# 5_-Motor_Driver_Schematic.net
KiCad netlist of a schematic drawn in Altium Designer
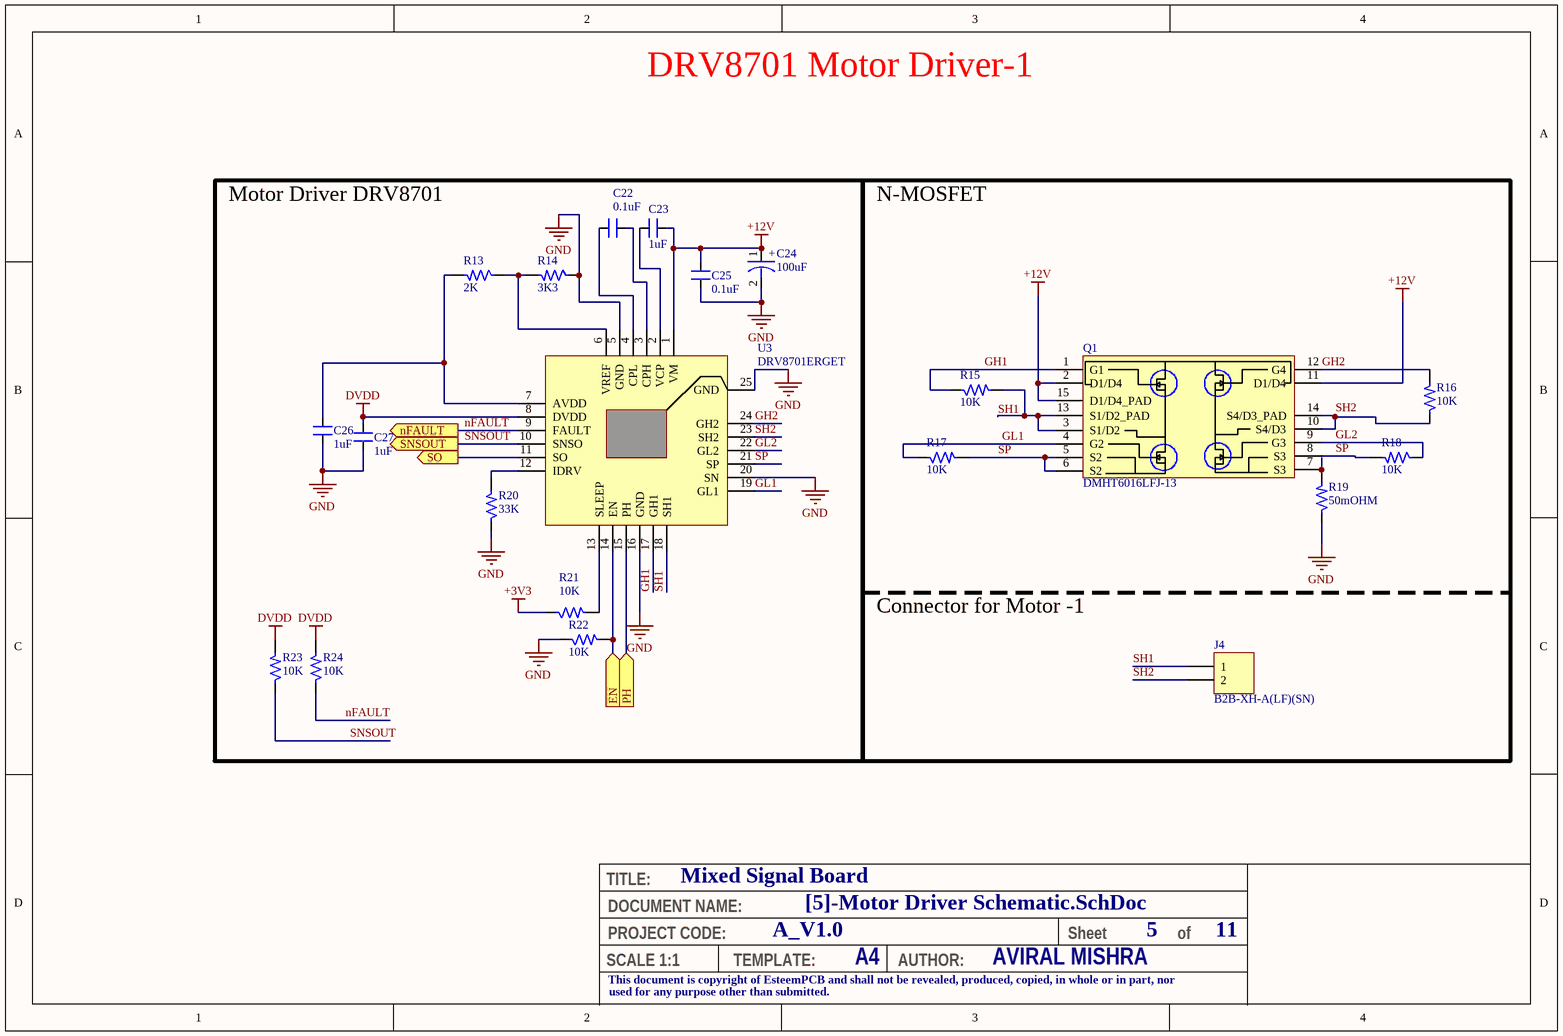
[diagram p0: [5]-Motor Driver Schematic.SchDoc]

(export (version "E")
  (design (tool "Eeschema 10.0.6"))
  (components
    (comp (ref "C22")
      (value "0.1uF")
      (footprint "CAP_0805")
      (description "0.1µF ±10% 50V Ceramic Capacitor X7R 0805 (2012 Metric)")
      (fields
        (field (name "MANUFACTURER") "Samsung")
        (field (name "MANUFACTURER PART NUMBER") "CL21B104KBCNNNC")
      )
      (libsource (lib "ESTEEMPCBLIB") (part "CAP_0.1uF-50V-10%-0805"))
    )
    (comp (ref "C23")
      (value "1uF")
      (footprint "CAP_0805")
      (description "1µF ±5% 50V Ceramic Capacitor X7R 0805 (2012 Metric)")
      (fields
        (field (name "MANUFACTURER") "Samsung")
        (field (name "MANUFACTURER PART NUMBER") "CC0805JKX7R9BB105")
      )
      (libsource (lib "ESTEEMPCBLIB") (part "CAP_1uF-50V-5%-0805"))
    )
    (comp (ref "C24")
      (value "100uF")
      (footprint "ACAP_P236_D305_H303_RAD")
      (description "100µF 25V Aluminum Electrolytic Capacitors Radial, Can - SMD 1000 Hrs @ 105°C")
      (fields
        (field (name "MANUFACTURER") "Nichicon")
        (field (name "MANUFACTURER PART NUMBER") "UWT1E101MCL1GS")
      )
      (libsource (lib "ESTEEMPCBLIB") (part "CAP-P_100uF-25V-20%-RAD"))
    )
    (comp (ref "C25")
      (value "0.1uF")
      (footprint "CAP_0805")
      (description "0.1µF ±10% 50V Ceramic Capacitor X7R 0805 (2012 Metric)")
      (fields
        (field (name "MANUFACTURER") "Samsung")
        (field (name "MANUFACTURER PART NUMBER") "CL21B104KBCNNNC")
      )
      (libsource (lib "ESTEEMPCBLIB") (part "CAP_0.1uF-50V-10%-0805"))
    )
    (comp (ref "C26")
      (value "1uF")
      (footprint "CAP_0805")
      (description "1µF ±5% 50V Ceramic Capacitor X7R 0805 (2012 Metric)")
      (fields
        (field (name "MANUFACTURER") "Samsung")
        (field (name "MANUFACTURER PART NUMBER") "CC0805JKX7R9BB105")
      )
      (libsource (lib "ESTEEMPCBLIB") (part "CAP_1uF-50V-5%-0805"))
    )
    (comp (ref "C27")
      (value "1uF")
      (footprint "CAP_0805")
      (description "1µF ±5% 50V Ceramic Capacitor X7R 0805 (2012 Metric)")
      (fields
        (field (name "MANUFACTURER") "Samsung")
        (field (name "MANUFACTURER PART NUMBER") "CC0805JKX7R9BB105")
      )
      (libsource (lib "ESTEEMPCBLIB") (part "CAP_1uF-50V-5%-0805"))
    )
    (comp (ref "J4")
      (value "B2B-XH-A(LF)(SN)")
      (footprint "CON2_100_B2B-XH-A_TH_ST")
      (description "2 Pins, 1 Row 2.54mm Pitch, Straight Connector, male")
      (fields (field (name "MANUFACTURER") "JST") (field (name "MATING PART NUMBER") "XHP-2"))
      (libsource (lib "ESTEEMPCBLIB") (part "CON-PLG_2X1-100-ST-TH"))
    )
    (comp (ref "Q1")
      (value "DMHT6016LFJ-13")
      (footprint "DFN5045-12_33_212_27X15_SMD_1")
      (description "Mosfet Array 4 N-Channel 14.8A (Ta) Surface Mount V-DFN5045-12")
      (fields (field (name "MANUFACTURER") "ON Semiconductor"))
      (libsource (lib "ESTEEMPCBLIB") (part "MOSFET-N_60V-14.8A-V-DFN5045-12"))
    )
    (comp (ref "R13")
      (value "2K")
      (footprint "RES_0603")
      (fields
        (field (name "MANUFACTURER") "Stackpole Electronics")
        (field (name "MANUFACTURER PART NUMBER") "RNCP0603FTD2K00")
      )
      (libsource (lib "ESTEEMPCBLIB") (part "RES_2K-0.125W-1%-0603"))
    )
    (comp (ref "R14")
      (value "3K3")
      (footprint "RES_0603")
      (description "3.3 kOhms ±1% 0.1W, 1/10W Chip Resistor 0603 (1608 Metric) Automotive AEC-Q200 Thick Film")
      (fields (field (name "MANUFACTURER") "Wilson") (field (name "MANUFACTURER PART NUMBER") "WR06X3301FTL"))
      (libsource (lib "ESTEEMPCBLIB") (part "RES_3.3K-0.1W-1%-0603"))
    )
    (comp (ref "R15")
      (value "10K")
      (footprint "RES_0603")
      (description "10 kOhms ±1% 0.1W, 1/10W Chip Resistor 0603 (1608 Metric) Automotive AEC-Q200 Thick Film")
      (fields (field (name "MANUFACTURER") "Walsin") (field (name "MANUFACTURER PART NUMBER") "WR06X1002FTL"))
      (libsource (lib "ESTEEMPCBLIB") (part "RES_10K-0.1W-1%-0603"))
    )
    (comp (ref "R16")
      (value "10K")
      (footprint "RES_0603")
      (description "10 kOhms ±1% 0.1W, 1/10W Chip Resistor 0603 (1608 Metric) Automotive AEC-Q200 Thick Film")
      (fields (field (name "MANUFACTURER") "Walsin") (field (name "MANUFACTURER PART NUMBER") "WR06X1002FTL"))
      (libsource (lib "ESTEEMPCBLIB") (part "RES_10K-0.1W-1%-0603"))
    )
    (comp (ref "R17")
      (value "10K")
      (footprint "RES_0603")
      (description "10 kOhms ±1% 0.1W, 1/10W Chip Resistor 0603 (1608 Metric) Automotive AEC-Q200 Thick Film")
      (fields (field (name "MANUFACTURER") "Walsin") (field (name "MANUFACTURER PART NUMBER") "WR06X1002FTL"))
      (libsource (lib "ESTEEMPCBLIB") (part "RES_10K-0.1W-1%-0603"))
    )
    (comp (ref "R18")
      (value "10K")
      (footprint "RES_0603")
      (description "10 kOhms ±1% 0.1W, 1/10W Chip Resistor 0603 (1608 Metric) Automotive AEC-Q200 Thick Film")
      (fields (field (name "MANUFACTURER") "Walsin") (field (name "MANUFACTURER PART NUMBER") "WR06X1002FTL"))
      (libsource (lib "ESTEEMPCBLIB") (part "RES_10K-0.1W-1%-0603"))
    )
    (comp (ref "R19")
      (value "50mOHM")
      (footprint "RES_2512")
      (fields
        (field (name "MANUFACTURER") "Yageo")
        (field (name "MANUFACTURER PART NUMBER") "PA2512FKF7W0R05E")
      )
      (libsource (lib "ESTEEMPCBLIB") (part "RES_50mOhm-2W-1%-2512"))
    )
    (comp (ref "R20")
      (value "33K")
      (footprint "RES_0805")
      (fields
        (field (name "MANUFACTURER") "Vishay BCcomponents")
        (field (name "MANUFACTURER PART NUMBER") "CRG0805F33K")
      )
      (libsource (lib "ESTEEMPCBLIB") (part "RES_33K-0.125W-1%-0805"))
    )
    (comp (ref "R21")
      (value "10K")
      (footprint "RES_0603")
      (description "10 kOhms ±1% 0.1W, 1/10W Chip Resistor 0603 (1608 Metric) Automotive AEC-Q200 Thick Film")
      (fields (field (name "MANUFACTURER") "Walsin") (field (name "MANUFACTURER PART NUMBER") "WR06X1002FTL"))
      (libsource (lib "ESTEEMPCBLIB") (part "RES_10K-0.1W-1%-0603"))
    )
    (comp (ref "R22")
      (value "10K")
      (footprint "RES_0603")
      (description "10 kOhms ±1% 0.1W, 1/10W Chip Resistor 0603 (1608 Metric) Automotive AEC-Q200 Thick Film")
      (fields (field (name "MANUFACTURER") "Walsin") (field (name "MANUFACTURER PART NUMBER") "WR06X1002FTL"))
      (libsource (lib "ESTEEMPCBLIB") (part "RES_10K-0.1W-1%-0603"))
    )
    (comp (ref "R23")
      (value "10K")
      (footprint "RES_0603")
      (description "10 kOhms ±1% 0.1W, 1/10W Chip Resistor 0603 (1608 Metric) Automotive AEC-Q200 Thick Film")
      (fields (field (name "MANUFACTURER") "Walsin") (field (name "MANUFACTURER PART NUMBER") "WR06X1002FTL"))
      (libsource (lib "ESTEEMPCBLIB") (part "RES_10K-0.1W-1%-0603"))
    )
    (comp (ref "R24")
      (value "10K")
      (footprint "RES_0603")
      (description "10 kOhms ±1% 0.1W, 1/10W Chip Resistor 0603 (1608 Metric) Automotive AEC-Q200 Thick Film")
      (fields (field (name "MANUFACTURER") "Walsin") (field (name "MANUFACTURER PART NUMBER") "WR06X1002FTL"))
      (libsource (lib "ESTEEMPCBLIB") (part "RES_10K-0.1W-1%-0603"))
    )
    (comp (ref "U3")
      (value "DRV8701ERGET")
      (footprint "VFQFN24_19.6_196_12X32_SMD_1")
      (description "Motor Driver Power MOSFET Parallel 24-VQFN (4x4)")
      (fields (field (name "MANUFACTURER") "Texas Instruments"))
      (libsource (lib "ESTEEMPCBLIB") (part "IC_DRV8701ERGET"))
    )
  )
  (nets
    (net (code "1") (name "+3V3") (class "Default")
      (node (ref "R21") (pin "1") (pinfunction "1_1") (pintype "passive"))
    )
    (net (code "2") (name "+12V") (class "Default")
      (node (ref "C23") (pin "2") (pinfunction "2_2") (pintype "passive"))
      (node (ref "C24") (pin "1") (pinfunction "1_1") (pintype "passive"))
      (node (ref "C25") (pin "2") (pinfunction "2_2") (pintype "passive"))
      (node (ref "Q1") (pin "11") (pinfunction "D1/D4_11") (pintype "passive"))
      (node (ref "Q1") (pin "15") (pinfunction "D1/D4_PAD_15") (pintype "passive"))
      (node (ref "Q1") (pin "2") (pinfunction "D1/D4_2") (pintype "passive"))
      (node (ref "U3") (pin "1") (pinfunction "VM_1") (pintype "passive"))
    )
    (net (code "3") (name "/EN") (class "Default")
      (node (ref "R22") (pin "2") (pinfunction "2_2") (pintype "passive"))
      (node (ref "U3") (pin "14") (pinfunction "EN_14") (pintype "passive"))
    )
    (net (code "4") (name "/GH1") (class "Default")
      (node (ref "Q1") (pin "1") (pinfunction "G1_1") (pintype "passive"))
      (node (ref "R15") (pin "1") (pinfunction "1_1") (pintype "passive"))
      (node (ref "U3") (pin "17") (pinfunction "GH1_17") (pintype "passive"))
    )
    (net (code "5") (name "/GH2") (class "Default")
      (node (ref "Q1") (pin "12") (pinfunction "G4_12") (pintype "passive"))
      (node (ref "R16") (pin "2") (pinfunction "2_2") (pintype "passive"))
      (node (ref "U3") (pin "24") (pinfunction "GH2_24") (pintype "passive"))
    )
    (net (code "6") (name "/GL1") (class "Default")
      (node (ref "Q1") (pin "4") (pinfunction "G2_4") (pintype "passive"))
      (node (ref "R17") (pin "1") (pinfunction "1_1") (pintype "passive"))
      (node (ref "U3") (pin "19") (pinfunction "GL1_19") (pintype "passive"))
    )
    (net (code "7") (name "/GL2") (class "Default")
      (node (ref "Q1") (pin "9") (pinfunction "G3_9") (pintype "passive"))
      (node (ref "R18") (pin "1") (pinfunction "1_1") (pintype "passive"))
      (node (ref "U3") (pin "22") (pinfunction "GL2_22") (pintype "passive"))
    )
    (net (code "8") (name "/PH") (class "Default")
      (node (ref "U3") (pin "15") (pinfunction "PH_15") (pintype "passive"))
    )
    (net (code "9") (name "/SH1") (class "Default")
      (node (ref "J4") (pin "1") (pinfunction "1_1") (pintype "passive"))
      (node (ref "Q1") (pin "13") (pinfunction "S1/D2_PAD_13") (pintype "passive"))
      (node (ref "Q1") (pin "3") (pinfunction "S1/D2_3") (pintype "passive"))
      (node (ref "R15") (pin "2") (pinfunction "2_2") (pintype "passive"))
      (node (ref "U3") (pin "18") (pinfunction "SH1_18") (pintype "passive"))
    )
    (net (code "10") (name "/SH2") (class "Default")
      (node (ref "J4") (pin "2") (pinfunction "2_2") (pintype "passive"))
      (node (ref "Q1") (pin "10") (pinfunction "S4/D3_10") (pintype "passive"))
      (node (ref "Q1") (pin "14") (pinfunction "S4/D3_PAD_14") (pintype "passive"))
      (node (ref "R16") (pin "1") (pinfunction "1_1") (pintype "passive"))
      (node (ref "U3") (pin "23") (pinfunction "SH2_23") (pintype "passive"))
    )
    (net (code "11") (name "/SNSOUT") (class "Default")
      (node (ref "R23") (pin "1") (pinfunction "1_1") (pintype "passive"))
      (node (ref "U3") (pin "10") (pinfunction "SNSO_10") (pintype "passive"))
    )
    (net (code "12") (name "/SO") (class "Default")
      (node (ref "U3") (pin "11") (pinfunction "SO_11") (pintype "passive"))
    )
    (net (code "13") (name "/SP") (class "Default")
      (node (ref "Q1") (pin "5") (pinfunction "S2_5") (pintype "passive"))
      (node (ref "Q1") (pin "6") (pinfunction "S2_6") (pintype "passive"))
      (node (ref "Q1") (pin "8") (pinfunction "S3_8") (pintype "passive"))
      (node (ref "R17") (pin "2") (pinfunction "2_2") (pintype "passive"))
      (node (ref "R18") (pin "2") (pinfunction "2_2") (pintype "passive"))
      (node (ref "U3") (pin "21") (pinfunction "SP_21") (pintype "passive"))
    )
    (net (code "14") (name "/nFAULT") (class "Default")
      (node (ref "R24") (pin "1") (pinfunction "1_1") (pintype "passive"))
      (node (ref "U3") (pin "9") (pinfunction "FAULT_9") (pintype "passive"))
    )
    (net (code "15") (name "DVDD") (class "Default")
      (node (ref "C27") (pin "2") (pinfunction "2_2") (pintype "passive"))
      (node (ref "R23") (pin "2") (pinfunction "2_2") (pintype "passive"))
      (node (ref "R24") (pin "2") (pinfunction "2_2") (pintype "passive"))
      (node (ref "U3") (pin "8") (pinfunction "DVDD_8") (pintype "passive"))
    )
    (net (code "16") (name "GND") (class "Default")
      (node (ref "C24") (pin "2") (pinfunction "2_2") (pintype "passive"))
      (node (ref "C25") (pin "1") (pinfunction "1_1") (pintype "passive"))
      (node (ref "C26") (pin "1") (pinfunction "1_1") (pintype "passive"))
      (node (ref "C27") (pin "1") (pinfunction "1_1") (pintype "passive"))
      (node (ref "R14") (pin "1") (pinfunction "1_1") (pintype "passive"))
      (node (ref "R19") (pin "1") (pinfunction "1_1") (pintype "passive"))
      (node (ref "R20") (pin "1") (pinfunction "1_1") (pintype "passive"))
      (node (ref "R22") (pin "1") (pinfunction "1_1") (pintype "passive"))
      (node (ref "U3") (pin "16") (pinfunction "GND_16") (pintype "passive"))
      (node (ref "U3") (pin "20") (pinfunction "SN_20") (pintype "passive"))
      (node (ref "U3") (pin "25") (pinfunction "GND_25") (pintype "passive"))
      (node (ref "U3") (pin "5") (pinfunction "GND_5") (pintype "passive"))
    )
    (net (code "17") (name "Net-(Q1-S3-Pad7)") (class "Default")
      (node (ref "Q1") (pin "7") (pinfunction "S3_7") (pintype "passive"))
      (node (ref "R19") (pin "2") (pinfunction "2_2") (pintype "passive"))
    )
    (net (code "18") (name "Net-(U3-AVDD)") (class "Default")
      (node (ref "C26") (pin "2") (pinfunction "2_2") (pintype "passive"))
      (node (ref "R13") (pin "2") (pinfunction "2_2") (pintype "passive"))
      (node (ref "U3") (pin "7") (pinfunction "AVDD_7") (pintype "passive"))
    )
    (net (code "19") (name "Net-(U3-CPH)") (class "Default")
      (node (ref "C22") (pin "1") (pinfunction "1_1") (pintype "passive"))
      (node (ref "U3") (pin "3") (pinfunction "CPH_3") (pintype "passive"))
    )
    (net (code "20") (name "Net-(U3-CPL)") (class "Default")
      (node (ref "C22") (pin "2") (pinfunction "2_2") (pintype "passive"))
      (node (ref "U3") (pin "4") (pinfunction "CPL_4") (pintype "passive"))
    )
    (net (code "21") (name "Net-(U3-IDRV)") (class "Default")
      (node (ref "R20") (pin "2") (pinfunction "2_2") (pintype "passive"))
      (node (ref "U3") (pin "12") (pinfunction "IDRV_12") (pintype "passive"))
    )
    (net (code "22") (name "Net-(U3-SLEEP)") (class "Default")
      (node (ref "R21") (pin "2") (pinfunction "2_2") (pintype "passive"))
      (node (ref "U3") (pin "13") (pinfunction "SLEEP_13") (pintype "passive"))
    )
    (net (code "23") (name "Net-(U3-VCP)") (class "Default")
      (node (ref "C23") (pin "1") (pinfunction "1_1") (pintype "passive"))
      (node (ref "U3") (pin "2") (pinfunction "VCP_2") (pintype "passive"))
    )
    (net (code "24") (name "Net-(U3-VREF)") (class "Default")
      (node (ref "R13") (pin "1") (pinfunction "1_1") (pintype "passive"))
      (node (ref "R14") (pin "2") (pinfunction "2_2") (pintype "passive"))
      (node (ref "U3") (pin "6") (pinfunction "VREF_6") (pintype "passive"))
    )
  )
)
